# Line_following_robot_101824.net
KiCad netlist of a schematic drawn in Altium Designer
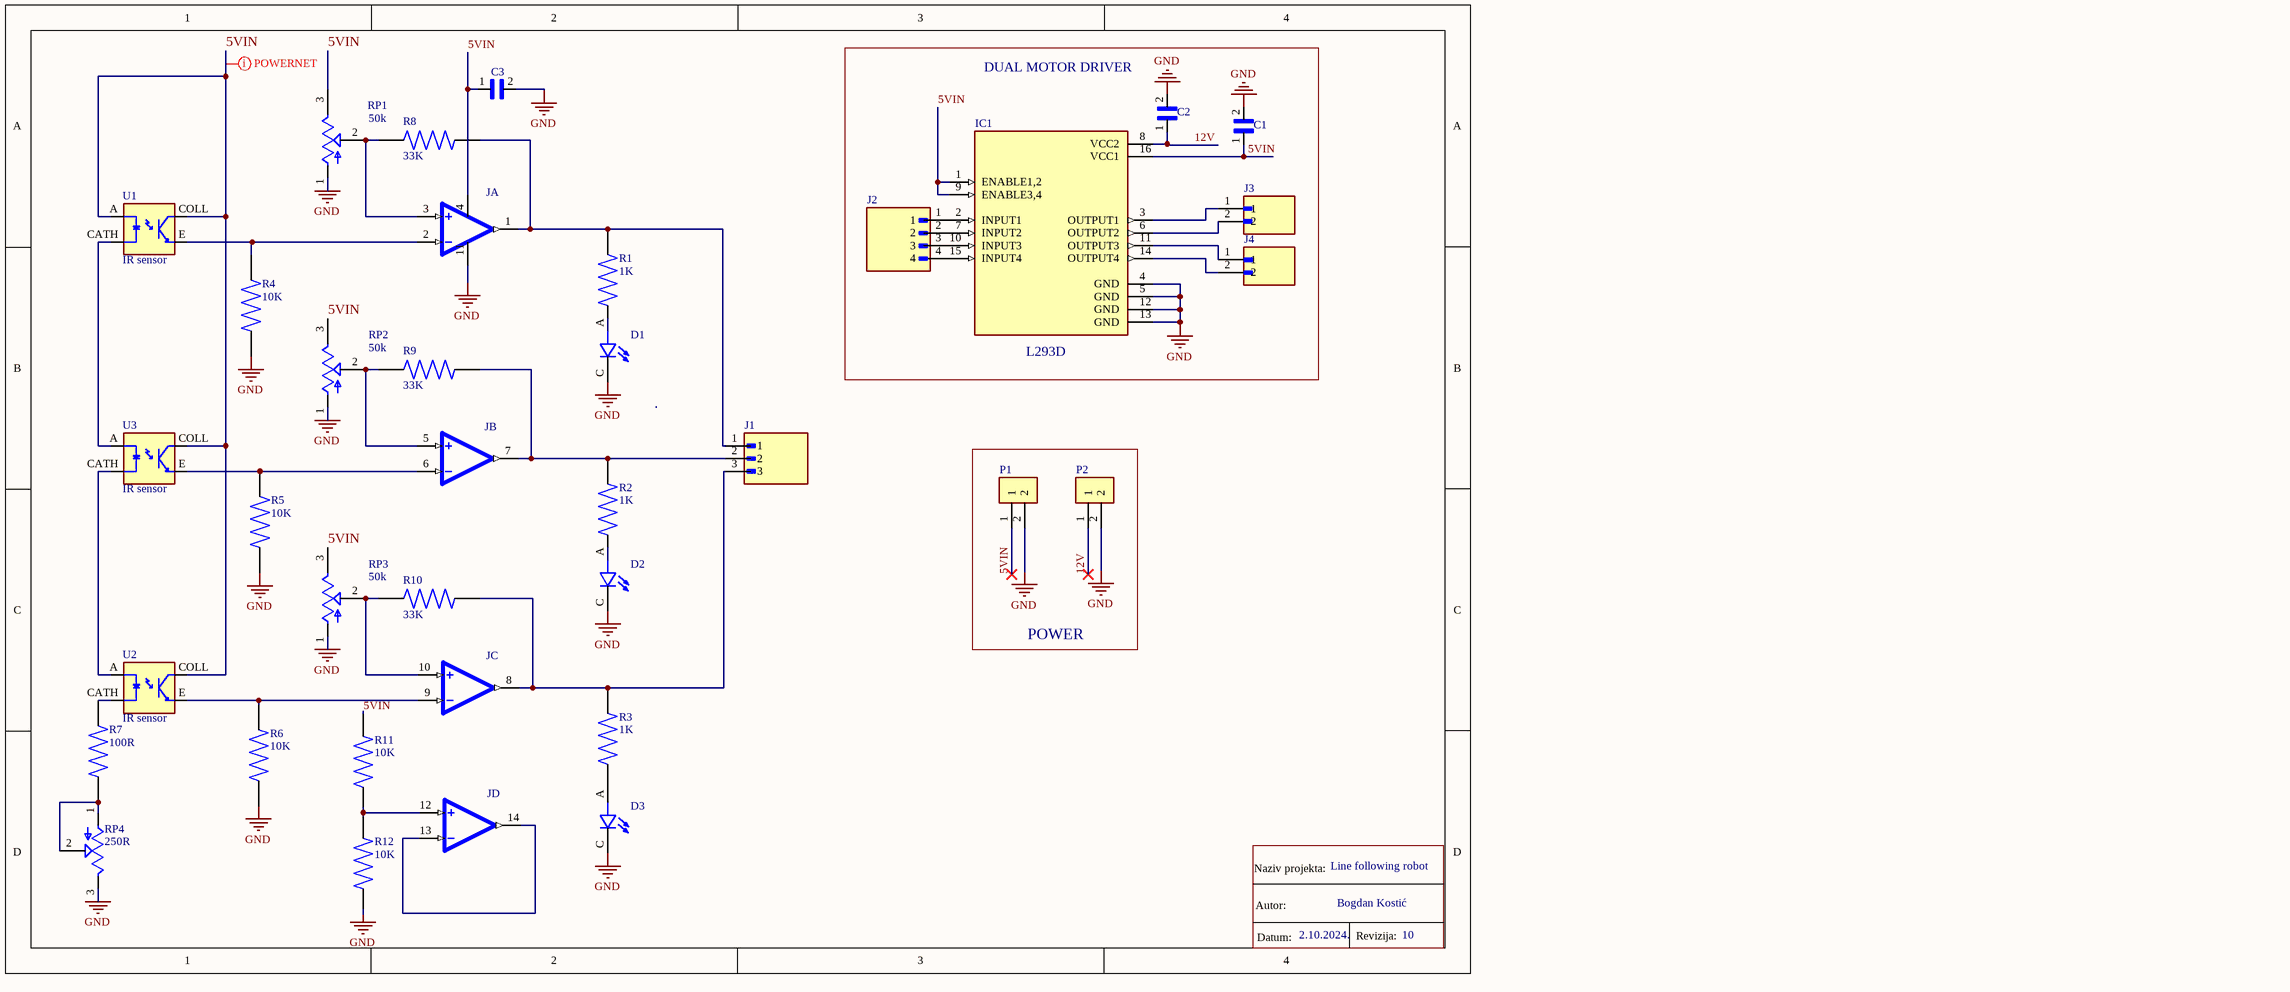
[diagram p0: Line following robot 101824.SchDoc]

(export (version "E")
  (design (tool "Eeschema 10.0.6"))
  (components
    (comp (ref "C1")
      (value "~")
      (footprint "CAPRB500W50L450T300H550")
      (description "Cap Ceramic 100nF 50V X7R 10% Radial 5mm 125Â°C Tape")
      (fields (field (name "MF") "TDK") (field (name "MP") "FG24X7R1H105KRT06"))
      (libsource (lib "") (part "FG24X7R1H105KRT06_1"))
    )
    (comp (ref "C2")
      (value "~")
      (footprint "CAPRB500W50L450T300H550")
      (description "Cap Ceramic 100nF 50V X7R 10% Radial 5mm 125Â°C Tape")
      (fields (field (name "MF") "TDK") (field (name "MP") "FG24X7R1H105KRT06"))
      (libsource (lib "") (part "FG24X7R1H105KRT06_1"))
    )
    (comp (ref "C3")
      (value "~")
      (footprint "CAPRB500W50L450T300H550")
      (description "Cap Ceramic 100nF 50V X7R 10% Radial 5mm 125Â°C Tape")
      (fields (field (name "MF") "TDK") (field (name "MP") "FG24X7R1H105KRT06"))
      (libsource (lib "Kondenzaotor ispravljen") (part "FG24X7R1H105KRT06"))
    )
    (comp (ref "D1")
      (value "~")
      (footprint "LEDRD254W50D500H1060")
      (description "LED 5mm Green 568nm 20mcd/10mA 60Â°")
      (fields (field (name "MF") "Kingbright") (field (name "MP") "L-53GD"))
      (libsource (lib "L-53GD") (part "L-53GD"))
    )
    (comp (ref "D2")
      (value "~")
      (footprint "LEDRD254W50D500H1060")
      (description "LED 5mm Green 568nm 20mcd/10mA 60Â°")
      (fields (field (name "MF") "Kingbright") (field (name "MP") "L-53GD"))
      (libsource (lib "L-53GD") (part "L-53GD"))
    )
    (comp (ref "D3")
      (value "~")
      (footprint "LEDRD254W50D500H1060")
      (description "LED 5mm Green 568nm 20mcd/10mA 60Â°")
      (fields (field (name "MF") "Kingbright") (field (name "MP") "L-53GD"))
      (libsource (lib "L-53GD") (part "L-53GD"))
    )
    (comp (ref "IC1")
      (value "L293D")
      (footprint "DIP880W50P254L2000H510Q16")
      (description "Bipolar Motor Driver - Parallel 16-PowerDIP")
      (fields (field (name "MF") "STMicroelectronics"))
      (libsource (lib "L293D") (part "L293D"))
    )
    (comp (ref "J")
      (value "~")
      (footprint "DIP825W47P254L1917H533Q14")
      (description "Quad, 30-V, 1.2-MHz operational amplifier")
      (fields (field (name "MF") "Texas Instruments") (field (name "MP") "LM324N"))
      (libsource (lib "LM324N_OPAMPSchLib") (part "LM324N/NOPB"))
    )
    (comp (ref "J1")
      (value "~")
      (footprint "HARWIN_M20-9990345")
      (fields (field (name "MF") "Harwin") (field (name "MP") "M20-9990345"))
      (libsource (lib "3 PIN HEADER") (part "M20-9990345"))
    )
    (comp (ref "J2")
      (value "~")
      (footprint "4 pin header 1 2 3 4")
      (fields (field (name "MP") "MTSW-104-08-L-S-315"))
      (libsource (lib "4 pin header izmenjen") (part "MTSW-104-08-L-S-315"))
    )
    (comp (ref "J3")
      (value "~")
      (footprint "TE_5-146278-2")
      (description "02 MODII HDR SRST B/A .100CL")
      (fields (field (name "MF") "TE Connectivity") (field (name "MP") "5-146278-2"))
      (libsource (lib "2PINKONEKTORSchLib") (part "5-146278-2"))
    )
    (comp (ref "J4")
      (value "~")
      (footprint "TE_5-146278-2")
      (description "02 MODII HDR SRST B/A .100CL")
      (fields (field (name "MF") "TE Connectivity") (field (name "MP") "5-146278-2"))
      (libsource (lib "2PINKONEKTORSchLib") (part "5-146278-2"))
    )
    (comp (ref "P1")
      (value "~")
      (footprint "TE_282837-2")
      (description "2 pin terminal")
      (fields (field (name "MF") "TE Connectivity") (field (name "MP") "282837-2"))
      (libsource (lib "terminal") (part "282837-2"))
    )
    (comp (ref "P2")
      (value "~")
      (footprint "TE_282837-2")
      (description "2 pin terminal")
      (fields (field (name "MF") "TE Connectivity") (field (name "MP") "282837-2"))
      (libsource (lib "terminal") (part "282837-2"))
    )
    (comp (ref "R1")
      (value "1K")
      (footprint "Otpornik 1k Ohm")
      (description "100 Ohms Â±1% 0.25W, 1/4W Through Hole Resistor Axial Metal Film")
      (fields (field (name "MF") "Yageo") (field (name "MP") "MFR-25FRF52-100R"))
      (libsource (lib "1k Ohm resistor") (part "MFR-25FRF52-100R"))
    )
    (comp (ref "R2")
      (value "1K")
      (footprint "Otpornik 1k Ohm")
      (description "100 Ohms Â±1% 0.25W, 1/4W Through Hole Resistor Axial Metal Film")
      (fields (field (name "MF") "Yageo") (field (name "MP") "MFR-25FRF52-100R"))
      (libsource (lib "1k Ohm resistor") (part "MFR-25FRF52-100R"))
    )
    (comp (ref "R3")
      (value "1K")
      (footprint "Otpornik 1k Ohm")
      (description "100 Ohms Â±1% 0.25W, 1/4W Through Hole Resistor Axial Metal Film")
      (fields (field (name "MF") "Yageo") (field (name "MP") "MFR-25FRF52-100R"))
      (libsource (lib "1k Ohm resistor") (part "MFR-25FRF52-100R"))
    )
    (comp (ref "R4")
      (value "10K")
      (footprint "10k")
      (description "100 Ohms Â±1% 0.25W, 1/4W Through Hole Resistor Axial Metal Film")
      (fields (field (name "MF") "Yageo") (field (name "MP") "MFR-25FRF52-100R"))
      (libsource (lib "10k Ohm resistor") (part "MFR-25FRF52-100R"))
    )
    (comp (ref "R5")
      (value "10K")
      (footprint "10k")
      (description "100 Ohms Â±1% 0.25W, 1/4W Through Hole Resistor Axial Metal Film")
      (fields (field (name "MF") "Yageo") (field (name "MP") "MFR-25FRF52-100R"))
      (libsource (lib "10k Ohm resistor") (part "MFR-25FRF52-100R"))
    )
    (comp (ref "R6")
      (value "10K")
      (footprint "10k")
      (description "100 Ohms Â±1% 0.25W, 1/4W Through Hole Resistor Axial Metal Film")
      (fields (field (name "MF") "Yageo") (field (name "MP") "MFR-25FRF52-100R"))
      (libsource (lib "10k Ohm resistor") (part "MFR-25FRF52-100R"))
    )
    (comp (ref "R7")
      (value "100R")
      (footprint "100R")
      (description "100 Ohms Â±1% 0.25W, 1/4W Through Hole Resistor Axial Metal Film")
      (fields (field (name "MF") "Yageo") (field (name "MP") "MFR-25FRF52-100R"))
      (libsource (lib "100R Ohm resistor") (part "MFR-25FRF52-100R"))
    )
    (comp (ref "R8")
      (value "33K")
      (footprint "RESAD1100W55L680D260")
      (description "1.07 kOhms Â±1% 0.25W, 1/4W Through Hole Resistor Axial - Metal Film")
      (fields (field (name "MF") "Yageo") (field (name "MP") "MFR-25FBF52-1K"))
      (libsource (lib "Otpornik 33k") (part "MFR-25FBF52-1K"))
    )
    (comp (ref "R9")
      (value "33K")
      (footprint "RESAD1100W55L680D260")
      (description "1.07 kOhms Â±1% 0.25W, 1/4W Through Hole Resistor Axial - Metal Film")
      (fields (field (name "MF") "Yageo") (field (name "MP") "MFR-25FBF52-1K"))
      (libsource (lib "Otpornik 33k") (part "MFR-25FBF52-1K"))
    )
    (comp (ref "R10")
      (value "33K")
      (footprint "RESAD1100W55L680D260")
      (description "1.07 kOhms Â±1% 0.25W, 1/4W Through Hole Resistor Axial - Metal Film")
      (fields (field (name "MF") "Yageo") (field (name "MP") "MFR-25FBF52-1K"))
      (libsource (lib "Otpornik 33k") (part "MFR-25FBF52-1K"))
    )
    (comp (ref "R11")
      (value "10K")
      (footprint "10k")
      (description "100 Ohms Â±1% 0.25W, 1/4W Through Hole Resistor Axial Metal Film")
      (fields (field (name "MF") "Yageo") (field (name "MP") "MFR-25FRF52-100R"))
      (libsource (lib "10k Ohm resistor") (part "MFR-25FRF52-100R"))
    )
    (comp (ref "R12")
      (value "10K")
      (footprint "10k")
      (description "100 Ohms Â±1% 0.25W, 1/4W Through Hole Resistor Axial Metal Film")
      (fields (field (name "MF") "Yageo") (field (name "MP") "MFR-25FRF52-100R"))
      (libsource (lib "10k Ohm resistor") (part "MFR-25FRF52-100R"))
    )
    (comp (ref "RP1")
      (value "50k")
      (footprint "TRIM_3296W-1-250")
      (description "50k Ohms 0.5W, 1/2W PC Pins Through Hole Trimmer Potentiometer Cermet 1.0 Turn Top Adjustment")
      (fields (field (name "MF") "Bourns") (field (name "MP") "3362P-1-251LF"))
      (libsource (lib "3362P-1-251LF") (part "3362P-1-251LF"))
    )
    (comp (ref "RP2")
      (value "50k")
      (footprint "TRIM_3296W-1-250")
      (description "50k Ohms 0.5W, 1/2W PC Pins Through Hole Trimmer Potentiometer Cermet 1.0 Turn Top Adjustment")
      (fields (field (name "MF") "Bourns") (field (name "MP") "3362P-1-251LF"))
      (libsource (lib "3362P-1-251LF") (part "3362P-1-251LF"))
    )
    (comp (ref "RP3")
      (value "50k")
      (footprint "TRIM_3296W-1-250")
      (description "50k Ohms 0.5W, 1/2W PC Pins Through Hole Trimmer Potentiometer Cermet 1.0 Turn Top Adjustment")
      (fields (field (name "MF") "Bourns") (field (name "MP") "3362P-1-251LF"))
      (libsource (lib "3362P-1-251LF") (part "3362P-1-251LF"))
    )
    (comp (ref "RP4")
      (value "250R")
      (footprint "TRIM_3296W-1-250")
      (description "250 Ohms 0.5W, 1/2W PC Pins Through Hole Trimmer Potentiometer Cermet 1.0 Turn Top Adjustment")
      (fields (field (name "MF") "Bourns") (field (name "MP") "3362P-1-251LF"))
      (libsource (lib "3362P-1-251LF") (part "3362P-1-251LF"))
    )
    (comp (ref "U1")
      (value "IR sensor")
      (footprint "OPTO_TCRT5000 verzija2")
      (description "950 nm 60 mA Through Hole Reflective Optical Sensor with Transistor Output")
      (fields (field (name "MP") "TCRT5000"))
      (libsource (lib "TCRT5000VERZIJA2SchLib") (part "TCRT5000"))
    )
    (comp (ref "U2")
      (value "IR sensor")
      (footprint "OPTO_TCRT5000 verzija2")
      (description "950 nm 60 mA Through Hole Reflective Optical Sensor with Transistor Output")
      (fields (field (name "MP") "TCRT5000"))
      (libsource (lib "TCRT5000VERZIJA2SchLib") (part "TCRT5000"))
    )
    (comp (ref "U3")
      (value "IR sensor")
      (footprint "OPTO_TCRT5000 verzija2")
      (description "950 nm 60 mA Through Hole Reflective Optical Sensor with Transistor Output")
      (fields (field (name "MP") "TCRT5000"))
      (libsource (lib "TCRT5000VERZIJA2SchLib") (part "TCRT5000"))
    )
  )
  (nets
    (net (code "1") (name "/5VIN") (class "Default")
      (node (ref "C1") (pin "1") (pinfunction "1_1") (pintype "passive"))
      (node (ref "C3") (pin "1") (pinfunction "1_1") (pintype "passive"))
      (node (ref "IC1") (pin "1") (pinfunction "ENABLE1,2_1") (pintype "input"))
      (node (ref "IC1") (pin "16") (pinfunction "VCC1_16") (pintype "power_in"))
      (node (ref "IC1") (pin "9") (pinfunction "ENABLE3,4_9") (pintype "input"))
      (node (ref "P1") (pin "1") (pinfunction "1_1") (pintype "passive"))
      (node (ref "R11") (pin "2") (pinfunction "2_2") (pintype "passive"))
      (node (ref "RP1") (pin "3") (pinfunction "CW_3") (pintype "passive"))
      (node (ref "RP2") (pin "3") (pinfunction "CW_3") (pintype "passive"))
      (node (ref "RP3") (pin "3") (pinfunction "CW_3") (pintype "passive"))
      (node (ref "U1") (pin "A") (pinfunction "A_A") (pintype "passive"))
      (node (ref "U1") (pin "COLL") (pinfunction "COLL_COLL") (pintype "passive"))
      (node (ref "U2") (pin "COLL") (pinfunction "COLL_COLL") (pintype "passive"))
      (node (ref "U3") (pin "COLL") (pinfunction "COLL_COLL") (pintype "passive"))
    )
    (net (code "2") (name "/12V") (class "Default")
      (node (ref "C2") (pin "1") (pinfunction "1_1") (pintype "passive"))
      (node (ref "IC1") (pin "8") (pinfunction "VCC2_8") (pintype "power_in"))
      (node (ref "P2") (pin "1") (pinfunction "1_1") (pintype "passive"))
    )
    (net (code "3") (name "GND") (class "Default")
      (node (ref "C1") (pin "2") (pinfunction "2_2") (pintype "passive"))
      (node (ref "C2") (pin "2") (pinfunction "2_2") (pintype "passive"))
      (node (ref "C3") (pin "2") (pinfunction "2_2") (pintype "passive"))
      (node (ref "D1") (pin "C") (pinfunction "C_C") (pintype "passive"))
      (node (ref "D2") (pin "C") (pinfunction "C_C") (pintype "passive"))
      (node (ref "D3") (pin "C") (pinfunction "C_C") (pintype "passive"))
      (node (ref "IC1") (pin "12") (pinfunction "GND_12") (pintype "power_in"))
      (node (ref "IC1") (pin "13") (pinfunction "GND_13") (pintype "power_in"))
      (node (ref "IC1") (pin "4") (pinfunction "GND_4") (pintype "power_in"))
      (node (ref "IC1") (pin "5") (pinfunction "GND_5") (pintype "power_in"))
      (node (ref "P1") (pin "2") (pinfunction "2_2") (pintype "passive"))
      (node (ref "P2") (pin "2") (pinfunction "2_2") (pintype "passive"))
      (node (ref "R12") (pin "1") (pinfunction "1_1") (pintype "passive"))
      (node (ref "R4") (pin "1") (pinfunction "1_1") (pintype "passive"))
      (node (ref "R5") (pin "1") (pinfunction "1_1") (pintype "passive"))
      (node (ref "R6") (pin "1") (pinfunction "1_1") (pintype "passive"))
      (node (ref "RP1") (pin "1") (pinfunction "CCW_1") (pintype "passive"))
      (node (ref "RP2") (pin "1") (pinfunction "CCW_1") (pintype "passive"))
      (node (ref "RP3") (pin "1") (pinfunction "CCW_1") (pintype "passive"))
      (node (ref "RP4") (pin "3") (pinfunction "CW_3") (pintype "passive"))
    )
    (net (code "4") (name "Net-(D1-PadA)") (class "Default")
      (node (ref "D1") (pin "A") (pinfunction "A_A") (pintype "passive"))
      (node (ref "R1") (pin "2") (pinfunction "2_2") (pintype "passive"))
    )
    (net (code "5") (name "Net-(D2-PadA)") (class "Default")
      (node (ref "D2") (pin "A") (pinfunction "A_A") (pintype "passive"))
      (node (ref "R2") (pin "2") (pinfunction "2_2") (pintype "passive"))
    )
    (net (code "6") (name "Net-(D3-PadA)") (class "Default")
      (node (ref "D3") (pin "A") (pinfunction "A_A") (pintype "passive"))
      (node (ref "R3") (pin "2") (pinfunction "2_2") (pintype "passive"))
    )
    (net (code "7") (name "Net-(IC1-INPUT1)") (class "Default")
      (node (ref "IC1") (pin "2") (pinfunction "INPUT1_2") (pintype "input"))
      (node (ref "J2") (pin "1") (pinfunction "1_1") (pintype "passive"))
    )
    (net (code "8") (name "Net-(IC1-INPUT2)") (class "Default")
      (node (ref "IC1") (pin "7") (pinfunction "INPUT2_7") (pintype "input"))
      (node (ref "J2") (pin "2") (pinfunction "2_2") (pintype "passive"))
    )
    (net (code "9") (name "Net-(IC1-INPUT3)") (class "Default")
      (node (ref "IC1") (pin "10") (pinfunction "INPUT3_10") (pintype "input"))
      (node (ref "J2") (pin "3") (pinfunction "3_3") (pintype "passive"))
    )
    (net (code "10") (name "Net-(IC1-INPUT4)") (class "Default")
      (node (ref "IC1") (pin "15") (pinfunction "INPUT4_15") (pintype "input"))
      (node (ref "J2") (pin "4") (pinfunction "4_4") (pintype "passive"))
    )
    (net (code "11") (name "Net-(IC1-OUTPUT1)") (class "Default")
      (node (ref "IC1") (pin "3") (pinfunction "OUTPUT1_3") (pintype "output"))
      (node (ref "J3") (pin "1") (pinfunction "1_1") (pintype "passive"))
    )
    (net (code "12") (name "Net-(IC1-OUTPUT2)") (class "Default")
      (node (ref "IC1") (pin "6") (pinfunction "OUTPUT2_6") (pintype "output"))
      (node (ref "J3") (pin "2") (pinfunction "2_2") (pintype "passive"))
    )
    (net (code "13") (name "Net-(IC1-OUTPUT3)") (class "Default")
      (node (ref "IC1") (pin "11") (pinfunction "OUTPUT3_11") (pintype "output"))
      (node (ref "J4") (pin "1") (pinfunction "1_1") (pintype "passive"))
    )
    (net (code "14") (name "Net-(IC1-OUTPUT4)") (class "Default")
      (node (ref "IC1") (pin "14") (pinfunction "OUTPUT4_14") (pintype "output"))
      (node (ref "J4") (pin "2") (pinfunction "2_2") (pintype "passive"))
    )
    (net (code "15") (name "Net-(JA-1IN+)") (class "Default")
      (node (ref "J") (pin "3") (pinfunction "1IN+_3") (pintype "input"))
      (node (ref "R8") (pin "2") (pinfunction "2_2") (pintype "passive"))
      (node (ref "RP1") (pin "2") (pinfunction "WIPER_2") (pintype "passive"))
    )
    (net (code "16") (name "Net-(JA-1IN-)") (class "Default")
      (node (ref "J") (pin "2") (pinfunction "1IN-_2") (pintype "input"))
      (node (ref "R4") (pin "2") (pinfunction "2_2") (pintype "passive"))
      (node (ref "U1") (pin "E") (pinfunction "E_E") (pintype "passive"))
    )
    (net (code "17") (name "Net-(JA-1OUT)") (class "Default")
      (node (ref "J") (pin "1") (pinfunction "1OUT_1") (pintype "output"))
      (node (ref "J1") (pin "1") (pinfunction "1_1") (pintype "passive"))
      (node (ref "R1") (pin "1") (pinfunction "1_1") (pintype "passive"))
      (node (ref "R8") (pin "1") (pinfunction "1_1") (pintype "passive"))
    )
    (net (code "18") (name "Net-(JB-2IN+)") (class "Default")
      (node (ref "J") (pin "5") (pinfunction "2IN+_5") (pintype "input"))
      (node (ref "R9") (pin "2") (pinfunction "2_2") (pintype "passive"))
      (node (ref "RP2") (pin "2") (pinfunction "WIPER_2") (pintype "passive"))
    )
    (net (code "19") (name "Net-(JB-2IN-)") (class "Default")
      (node (ref "J") (pin "6") (pinfunction "2IN-_6") (pintype "input"))
      (node (ref "R5") (pin "2") (pinfunction "2_2") (pintype "passive"))
      (node (ref "U3") (pin "E") (pinfunction "E_E") (pintype "passive"))
    )
    (net (code "20") (name "Net-(JB-2OUT)") (class "Default")
      (node (ref "J") (pin "7") (pinfunction "2OUT_7") (pintype "output"))
      (node (ref "J1") (pin "2") (pinfunction "2_2") (pintype "passive"))
      (node (ref "R2") (pin "1") (pinfunction "1_1") (pintype "passive"))
      (node (ref "R9") (pin "1") (pinfunction "1_1") (pintype "passive"))
    )
    (net (code "21") (name "Net-(JC-3IN+)") (class "Default")
      (node (ref "J") (pin "10") (pinfunction "3IN+_10") (pintype "input"))
      (node (ref "R10") (pin "2") (pinfunction "2_2") (pintype "passive"))
      (node (ref "RP3") (pin "2") (pinfunction "WIPER_2") (pintype "passive"))
    )
    (net (code "22") (name "Net-(JC-3IN-)") (class "Default")
      (node (ref "J") (pin "9") (pinfunction "3IN-_9") (pintype "input"))
      (node (ref "R6") (pin "2") (pinfunction "2_2") (pintype "passive"))
      (node (ref "U2") (pin "E") (pinfunction "E_E") (pintype "passive"))
    )
    (net (code "23") (name "Net-(JC-3OUT)") (class "Default")
      (node (ref "J") (pin "8") (pinfunction "3OUT_8") (pintype "output"))
      (node (ref "J1") (pin "3") (pinfunction "3_3") (pintype "passive"))
      (node (ref "R10") (pin "1") (pinfunction "1_1") (pintype "passive"))
      (node (ref "R3") (pin "1") (pinfunction "1_1") (pintype "passive"))
    )
    (net (code "24") (name "Net-(JD-4IN+)") (class "Default")
      (node (ref "J") (pin "12") (pinfunction "4IN+_12") (pintype "input"))
      (node (ref "R11") (pin "1") (pinfunction "1_1") (pintype "passive"))
      (node (ref "R12") (pin "2") (pinfunction "2_2") (pintype "passive"))
    )
    (net (code "25") (name "Net-(JD-4IN-)") (class "Default")
      (node (ref "J") (pin "13") (pinfunction "4IN-_13") (pintype "input"))
      (node (ref "J") (pin "14") (pinfunction "4OUT_14") (pintype "output"))
    )
    (net (code "26") (name "Net-(R7-Pad2)") (class "Default")
      (node (ref "R7") (pin "2") (pinfunction "2_2") (pintype "passive"))
      (node (ref "U2") (pin "CATH") (pinfunction "CATH_CATH") (pintype "passive"))
    )
    (net (code "27") (name "Net-(RP4-CCW)") (class "Default")
      (node (ref "R7") (pin "1") (pinfunction "1_1") (pintype "passive"))
      (node (ref "RP4") (pin "1") (pinfunction "CCW_1") (pintype "passive"))
      (node (ref "RP4") (pin "2") (pinfunction "WIPER_2") (pintype "passive"))
    )
    (net (code "28") (name "Net-(U1-PadCATH)") (class "Default")
      (node (ref "U1") (pin "CATH") (pinfunction "CATH_CATH") (pintype "passive"))
      (node (ref "U3") (pin "A") (pinfunction "A_A") (pintype "passive"))
    )
    (net (code "29") (name "Net-(U2-PadA)") (class "Default")
      (node (ref "U2") (pin "A") (pinfunction "A_A") (pintype "passive"))
      (node (ref "U3") (pin "CATH") (pinfunction "CATH_CATH") (pintype "passive"))
    )
    (net (code "30") (name "unconnected-(JA-GND-Pad11)") (class "Default")
      (node (ref "J") (pin "11") (pinfunction "GND_11") (pintype "power_in"))
    )
    (net (code "31") (name "unconnected-(JA-V+-Pad4)") (class "Default")
      (node (ref "J") (pin "4") (pinfunction "V+_4") (pintype "power_in"))
    )
  )
)
